# CPU.net
KiCad netlist of a schematic drawn in Altium Designer
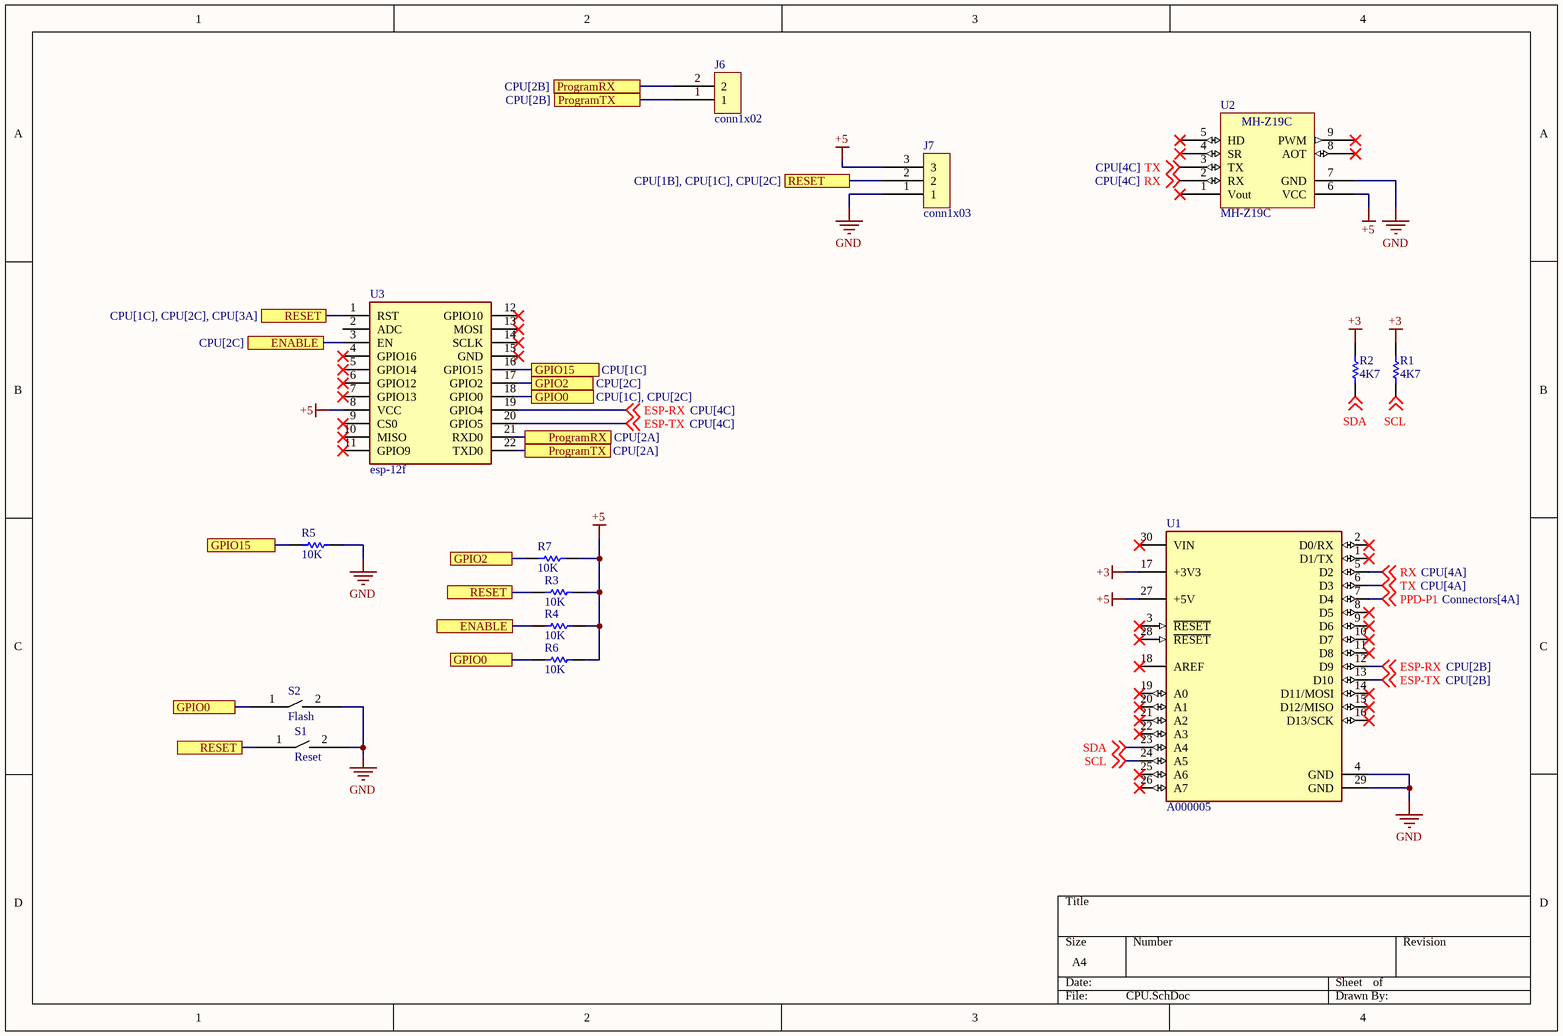
[diagram p0: CPU.SchDoc]

(export (version "E")
  (design (tool "Eeschema 10.0.6"))
  (components
    (comp (ref "J6") (value "conn1x02") (footprint "conn1x02") (libsource (lib "Schlib1") (part "conn1x02")))
    (comp (ref "J7") (value "conn1x03") (footprint "conn1x03") (libsource (lib "Schlib1") (part "conn1x03")))
    (comp (ref "R1")
      (value "4K7")
      (footprint "1206")
      (fields (field (name "MANUFACTURER") "Panasonic"))
      (libsource (lib "Schlib1") (part "CMP-2001-04375-5"))
    )
    (comp (ref "R2")
      (value "4K7")
      (footprint "1206")
      (fields (field (name "MANUFACTURER") "Panasonic"))
      (libsource (lib "Schlib1") (part "CMP-2001-04375-5"))
    )
    (comp (ref "R3")
      (value "10K")
      (footprint "RESC2013X70X40ML20T20")
      (description "Chip Resistor, 1 KOhm, +/- 1%, 0.125 W, -55 to 155 degC, 0805 (2012 Metric), RoHS, Tape and Reel")
      (fields (field (name "MANUFACTURER") "Panasonic"))
      (libsource (lib "Schlib1") (part "CMP-2001-04375-5"))
    )
    (comp (ref "R4")
      (value "10K")
      (footprint "RESC2013X70X40ML20T20")
      (description "Chip Resistor, 1 KOhm, +/- 1%, 0.125 W, -55 to 155 degC, 0805 (2012 Metric), RoHS, Tape and Reel")
      (fields (field (name "MANUFACTURER") "Panasonic"))
      (libsource (lib "Schlib1") (part "CMP-2001-04375-5"))
    )
    (comp (ref "R5")
      (value "10K")
      (footprint "RESC2013X70X40ML20T20")
      (description "Chip Resistor, 1 KOhm, +/- 1%, 0.125 W, -55 to 155 degC, 0805 (2012 Metric), RoHS, Tape and Reel")
      (fields (field (name "MANUFACTURER") "Panasonic"))
      (libsource (lib "Schlib1") (part "CMP-2001-04375-5"))
    )
    (comp (ref "R6")
      (value "10K")
      (footprint "RESC2013X70X40ML20T20")
      (description "Chip Resistor, 1 KOhm, +/- 1%, 0.125 W, -55 to 155 degC, 0805 (2012 Metric), RoHS, Tape and Reel")
      (fields (field (name "MANUFACTURER") "Panasonic"))
      (libsource (lib "Schlib1") (part "CMP-2001-04375-5"))
    )
    (comp (ref "R7")
      (value "10K")
      (footprint "RESC2013X70X40ML20T20")
      (description "Chip Resistor, 1 KOhm, +/- 1%, 0.125 W, -55 to 155 degC, 0805 (2012 Metric), RoHS, Tape and Reel")
      (fields (field (name "MANUFACTURER") "Panasonic"))
      (libsource (lib "Schlib1") (part "CMP-2001-04375-5"))
    )
    (comp (ref "S1") (value "Reset") (footprint "Switch") (libsource (lib "Schlib1") (part "Switch")))
    (comp (ref "S2") (value "Flash") (footprint "Switch") (libsource (lib "Schlib1") (part "Switch")))
    (comp (ref "U1")
      (value "A000005")
      (footprint "FP-A000005-MFG")
      (description "ARDUINO NANO ATMEGA328 EVAL BRD")
      (libsource (lib "Schlib1") (part "CMP-189986-000002-1"))
    )
    (comp (ref "U2") (value "MH-Z19C") (footprint "MH-Z19") (libsource (lib "Schlib1") (part "MH-Z19C")))
    (comp (ref "U3")
      (value "esp-12f")
      (footprint "SamacSys:esp12f")
      (description "Integrated Circuit")
      (libsource (lib "Schlib1") (part "esp-12f"))
    )
  )
  (nets
    (net (code "1") (name "+3") (class "Default")
      (node (ref "R1") (pin "2") (pinfunction "2_2") (pintype "passive"))
      (node (ref "R2") (pin "2") (pinfunction "2_2") (pintype "passive"))
      (node (ref "U1") (pin "17") (pinfunction "+3V3_17") (pintype "power_in"))
    )
    (net (code "2") (name "+5") (class "Default")
      (node (ref "J7") (pin "3") (pinfunction "3_3") (pintype "passive"))
      (node (ref "R3") (pin "2") (pinfunction "2_2") (pintype "passive"))
      (node (ref "R4") (pin "2") (pinfunction "2_2") (pintype "passive"))
      (node (ref "R6") (pin "2") (pinfunction "2_2") (pintype "passive"))
      (node (ref "R7") (pin "2") (pinfunction "2_2") (pintype "passive"))
      (node (ref "U1") (pin "27") (pinfunction "+5V_27") (pintype "power_in"))
      (node (ref "U2") (pin "6") (pinfunction "VCC_6") (pintype "power_in"))
      (node (ref "U3") (pin "8") (pinfunction "VCC_8") (pintype "passive"))
    )
    (net (code "3") (name "/ENABLE") (class "Default")
      (node (ref "R4") (pin "1") (pinfunction "1_1") (pintype "passive"))
      (node (ref "U3") (pin "3") (pinfunction "EN_3") (pintype "passive"))
    )
    (net (code "4") (name "/GPIO0") (class "Default")
      (node (ref "R6") (pin "1") (pinfunction "1_1") (pintype "passive"))
      (node (ref "S2") (pin "1") (pinfunction "1_1") (pintype "passive"))
      (node (ref "U3") (pin "18") (pinfunction "GPIO0_18") (pintype "passive"))
    )
    (net (code "5") (name "/GPIO2") (class "Default")
      (node (ref "R7") (pin "1") (pinfunction "1_1") (pintype "passive"))
      (node (ref "U3") (pin "17") (pinfunction "GPIO2_17") (pintype "passive"))
    )
    (net (code "6") (name "/GPIO15") (class "Default")
      (node (ref "R5") (pin "1") (pinfunction "1_1") (pintype "passive"))
      (node (ref "U3") (pin "16") (pinfunction "GPIO15_16") (pintype "passive"))
    )
    (net (code "7") (name "/ProgramRX") (class "Default")
      (node (ref "J6") (pin "2") (pinfunction "2_2") (pintype "passive"))
      (node (ref "U3") (pin "21") (pinfunction "RXD0_21") (pintype "passive"))
    )
    (net (code "8") (name "/ProgramTX") (class "Default")
      (node (ref "J6") (pin "1") (pinfunction "1_1") (pintype "passive"))
      (node (ref "U3") (pin "22") (pinfunction "TXD0_22") (pintype "passive"))
    )
    (net (code "9") (name "/RESET") (class "Default")
      (node (ref "J7") (pin "2") (pinfunction "2_2") (pintype "passive"))
      (node (ref "R3") (pin "1") (pinfunction "1_1") (pintype "passive"))
      (node (ref "S1") (pin "1") (pinfunction "1_1") (pintype "passive"))
      (node (ref "U3") (pin "1") (pinfunction "RST_1") (pintype "passive"))
    )
    (net (code "10") (name "ESP-RX") (class "Default")
      (node (ref "U1") (pin "12") (pinfunction "D9_12") (pintype "bidirectional"))
      (node (ref "U3") (pin "19") (pinfunction "GPIO4_19") (pintype "passive"))
    )
    (net (code "11") (name "ESP-TX") (class "Default")
      (node (ref "U1") (pin "13") (pinfunction "D10_13") (pintype "bidirectional"))
      (node (ref "U3") (pin "20") (pinfunction "GPIO5_20") (pintype "passive"))
    )
    (net (code "12") (name "GND") (class "Default")
      (node (ref "J7") (pin "1") (pinfunction "1_1") (pintype "passive"))
      (node (ref "R5") (pin "2") (pinfunction "2_2") (pintype "passive"))
      (node (ref "S1") (pin "2") (pinfunction "2_2") (pintype "passive"))
      (node (ref "S2") (pin "2") (pinfunction "2_2") (pintype "passive"))
      (node (ref "U1") (pin "29") (pinfunction "GND_29") (pintype "power_in"))
      (node (ref "U1") (pin "4") (pinfunction "GND_4") (pintype "power_in"))
      (node (ref "U2") (pin "7") (pinfunction "GND_7") (pintype "power_in"))
    )
    (net (code "13") (name "PPD-P1") (class "Default")
      (node (ref "U1") (pin "7") (pinfunction "D4_7") (pintype "bidirectional"))
    )
    (net (code "14") (name "RX") (class "Default")
      (node (ref "U1") (pin "5") (pinfunction "D2_5") (pintype "bidirectional"))
      (node (ref "U2") (pin "2") (pinfunction "RX_2") (pintype "bidirectional"))
    )
    (net (code "15") (name "SCL") (class "Default")
      (node (ref "R1") (pin "1") (pinfunction "1_1") (pintype "passive"))
      (node (ref "U1") (pin "24") (pinfunction "A5_24") (pintype "bidirectional"))
    )
    (net (code "16") (name "SDA") (class "Default")
      (node (ref "R2") (pin "1") (pinfunction "1_1") (pintype "passive"))
      (node (ref "U1") (pin "23") (pinfunction "A4_23") (pintype "bidirectional"))
    )
    (net (code "17") (name "TX") (class "Default")
      (node (ref "U1") (pin "6") (pinfunction "D3_6") (pintype "bidirectional"))
      (node (ref "U2") (pin "3") (pinfunction "TX_3") (pintype "bidirectional"))
    )
    (net (code "18") (name "unconnected-(U1-A0-Pad19)") (class "Default")
      (node (ref "U1") (pin "19") (pinfunction "A0_19") (pintype "bidirectional+no_connect"))
    )
    (net (code "19") (name "unconnected-(U1-A1-Pad20)") (class "Default")
      (node (ref "U1") (pin "20") (pinfunction "A1_20") (pintype "bidirectional+no_connect"))
    )
    (net (code "20") (name "unconnected-(U1-A2-Pad21)") (class "Default")
      (node (ref "U1") (pin "21") (pinfunction "A2_21") (pintype "bidirectional+no_connect"))
    )
    (net (code "21") (name "unconnected-(U1-A3-Pad22)") (class "Default")
      (node (ref "U1") (pin "22") (pinfunction "A3_22") (pintype "bidirectional+no_connect"))
    )
    (net (code "22") (name "unconnected-(U1-A6-Pad25)") (class "Default")
      (node (ref "U1") (pin "25") (pinfunction "A6_25") (pintype "bidirectional+no_connect"))
    )
    (net (code "23") (name "unconnected-(U1-A7-Pad26)") (class "Default")
      (node (ref "U1") (pin "26") (pinfunction "A7_26") (pintype "bidirectional+no_connect"))
    )
    (net (code "24") (name "unconnected-(U1-AREF-Pad18)") (class "Default")
      (node (ref "U1") (pin "18") (pinfunction "AREF_18") (pintype "passive+no_connect"))
    )
    (net (code "25") (name "unconnected-(U1-D0{slash}RX-Pad2)") (class "Default")
      (node (ref "U1") (pin "2") (pinfunction "D0/RX_2") (pintype "bidirectional+no_connect"))
    )
    (net (code "26") (name "unconnected-(U1-D1{slash}TX-Pad1)") (class "Default")
      (node (ref "U1") (pin "1") (pinfunction "D1/TX_1") (pintype "bidirectional+no_connect"))
    )
    (net (code "27") (name "unconnected-(U1-D5-Pad8)") (class "Default")
      (node (ref "U1") (pin "8") (pinfunction "D5_8") (pintype "bidirectional+no_connect"))
    )
    (net (code "28") (name "unconnected-(U1-D6-Pad9)") (class "Default")
      (node (ref "U1") (pin "9") (pinfunction "D6_9") (pintype "bidirectional+no_connect"))
    )
    (net (code "29") (name "unconnected-(U1-D7-Pad10)") (class "Default")
      (node (ref "U1") (pin "10") (pinfunction "D7_10") (pintype "bidirectional+no_connect"))
    )
    (net (code "30") (name "unconnected-(U1-D8-Pad11)") (class "Default")
      (node (ref "U1") (pin "11") (pinfunction "D8_11") (pintype "bidirectional+no_connect"))
    )
    (net (code "31") (name "unconnected-(U1-D11{slash}MOSI-Pad14)") (class "Default")
      (node (ref "U1") (pin "14") (pinfunction "D11/MOSI_14") (pintype "bidirectional+no_connect"))
    )
    (net (code "32") (name "unconnected-(U1-D12{slash}MISO-Pad15)") (class "Default")
      (node (ref "U1") (pin "15") (pinfunction "D12/MISO_15") (pintype "bidirectional+no_connect"))
    )
    (net (code "33") (name "unconnected-(U1-D13{slash}SCK-Pad16)") (class "Default")
      (node (ref "U1") (pin "16") (pinfunction "D13/SCK_16") (pintype "bidirectional+no_connect"))
    )
    (net (code "34") (name "unconnected-(U1-VIN-Pad30)") (class "Default")
      (node (ref "U1") (pin "30") (pinfunction "VIN_30") (pintype "power_in+no_connect"))
    )
    (net (code "35") (name "unconnected-(U1-~{RESET}-Pad3)") (class "Default")
      (node (ref "U1") (pin "3") (pinfunction "~{RESET}_3") (pintype "input+no_connect"))
    )
    (net (code "36") (name "unconnected-(U1-~{RESET}-Pad28)") (class "Default")
      (node (ref "U1") (pin "28") (pinfunction "~{RESET}_28") (pintype "input+no_connect"))
    )
    (net (code "37") (name "unconnected-(U2-AOT-Pad8)") (class "Default")
      (node (ref "U2") (pin "8") (pinfunction "AOT_8") (pintype "bidirectional+no_connect"))
    )
    (net (code "38") (name "unconnected-(U2-HD-Pad5)") (class "Default")
      (node (ref "U2") (pin "5") (pinfunction "HD_5") (pintype "bidirectional+no_connect"))
    )
    (net (code "39") (name "unconnected-(U2-PWM-Pad9)") (class "Default")
      (node (ref "U2") (pin "9") (pinfunction "PWM_9") (pintype "output+no_connect"))
    )
    (net (code "40") (name "unconnected-(U2-SR-Pad4)") (class "Default")
      (node (ref "U2") (pin "4") (pinfunction "SR_4") (pintype "bidirectional+no_connect"))
    )
    (net (code "41") (name "unconnected-(U2-Vout-Pad1)") (class "Default")
      (node (ref "U2") (pin "1") (pinfunction "Vout_1") (pintype "power_in+no_connect"))
    )
    (net (code "42") (name "unconnected-(U3-ADC-Pad2)") (class "Default")
      (node (ref "U3") (pin "2") (pinfunction "ADC_2") (pintype "passive"))
    )
    (net (code "43") (name "unconnected-(U3-CS0-Pad9)") (class "Default")
      (node (ref "U3") (pin "9") (pinfunction "CS0_9") (pintype "passive+no_connect"))
    )
    (net (code "44") (name "unconnected-(U3-GND-Pad15)") (class "Default")
      (node (ref "U3") (pin "15") (pinfunction "GND_15") (pintype "passive+no_connect"))
    )
    (net (code "45") (name "unconnected-(U3-GPIO9-Pad11)") (class "Default")
      (node (ref "U3") (pin "11") (pinfunction "GPIO9_11") (pintype "passive+no_connect"))
    )
    (net (code "46") (name "unconnected-(U3-GPIO10-Pad12)") (class "Default")
      (node (ref "U3") (pin "12") (pinfunction "GPIO10_12") (pintype "passive+no_connect"))
    )
    (net (code "47") (name "unconnected-(U3-GPIO12-Pad6)") (class "Default")
      (node (ref "U3") (pin "6") (pinfunction "GPIO12_6") (pintype "passive+no_connect"))
    )
    (net (code "48") (name "unconnected-(U3-GPIO13-Pad7)") (class "Default")
      (node (ref "U3") (pin "7") (pinfunction "GPIO13_7") (pintype "passive+no_connect"))
    )
    (net (code "49") (name "unconnected-(U3-GPIO14-Pad5)") (class "Default")
      (node (ref "U3") (pin "5") (pinfunction "GPIO14_5") (pintype "passive+no_connect"))
    )
    (net (code "50") (name "unconnected-(U3-GPIO16-Pad4)") (class "Default")
      (node (ref "U3") (pin "4") (pinfunction "GPIO16_4") (pintype "passive+no_connect"))
    )
    (net (code "51") (name "unconnected-(U3-MISO-Pad10)") (class "Default")
      (node (ref "U3") (pin "10") (pinfunction "MISO_10") (pintype "passive+no_connect"))
    )
    (net (code "52") (name "unconnected-(U3-MOSI-Pad13)") (class "Default")
      (node (ref "U3") (pin "13") (pinfunction "MOSI_13") (pintype "passive+no_connect"))
    )
    (net (code "53") (name "unconnected-(U3-SCLK-Pad14)") (class "Default")
      (node (ref "U3") (pin "14") (pinfunction "SCLK_14") (pintype "passive+no_connect"))
    )
  )
)
